# Adafruit_PCF8523_RTC.net
KiCad netlist of a schematic drawn in EAGLE
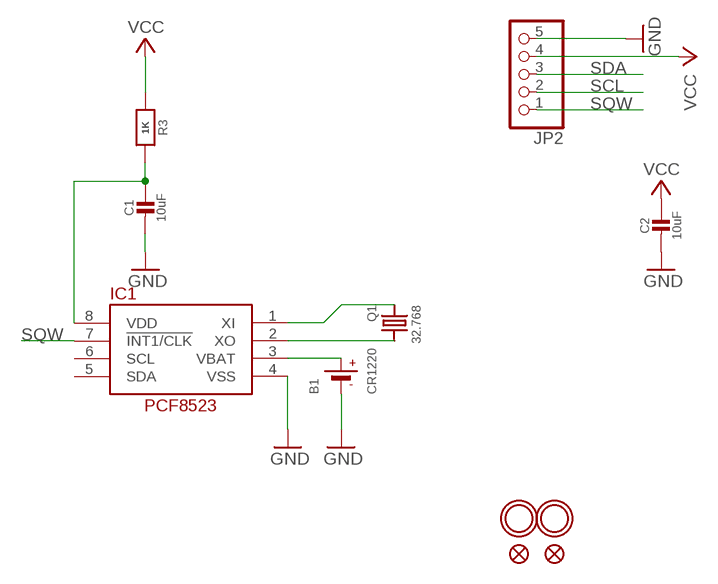
[diagram p0: schematic, sheet 1]

(export (version "E")
  (design (tool "Eeschema 10.0.6"))
  (components
    (comp (ref "B1")
      (value "CR1220")
      (footprint "eagle-import:CR1220")
      (libsource (lib "eagle-import") (part "BATTERYCR1220_SMT"))
    )
    (comp (ref "C1")
      (value "10uF")
      (footprint "eagle-import:0805-NO")
      (libsource (lib "eagle-import") (part "CAP_CERAMIC0805-NOOUTLINE"))
    )
    (comp (ref "C2")
      (value "10uF")
      (footprint "eagle-import:0805-NO")
      (libsource (lib "eagle-import") (part "CAP_CERAMIC0805-NOOUTLINE"))
    )
    (comp (ref "FID1")
      (value "FIDUCIAL\"\"")
      (footprint "eagle-import:FIDUCIAL_1MM")
      (libsource (lib "eagle-import") (part "FIDUCIAL{dblquote}{dblquote}"))
    )
    (comp (ref "FID2")
      (value "FIDUCIAL\"\"")
      (footprint "eagle-import:FIDUCIAL_1MM")
      (libsource (lib "eagle-import") (part "FIDUCIAL{dblquote}{dblquote}"))
    )
    (comp (ref "IC1")
      (value "RTC_PCF8523T")
      (footprint "eagle-import:SOIC8_150MIL")
      (libsource (lib "eagle-import") (part "RTC_PCF8523T"))
    )
    (comp (ref "JP2")
      (value "HEADER-1X576MIL")
      (footprint "eagle-import:1X05_ROUND_76")
      (libsource (lib "eagle-import") (part "HEADER-1X576MIL"))
    )
    (comp (ref "Q1")
      (value "32.768")
      (footprint "eagle-import:CRYSTAL_8X3.8")
      (libsource (lib "eagle-import") (part "CRYSTAL8.0X3.8"))
    )
    (comp (ref "R3")
      (value "1K")
      (footprint "eagle-import:0805-NO")
      (libsource (lib "eagle-import") (part "RESISTOR0805_NOOUTLINE"))
    )
    (comp (ref "U$1")
      (value "MOUNTINGHOLE2.0")
      (footprint "eagle-import:MOUNTINGHOLE_2.0_PLATED")
      (libsource (lib "eagle-import") (part "MOUNTINGHOLE2.0"))
    )
    (comp (ref "U$4")
      (value "MOUNTINGHOLE2.0")
      (footprint "eagle-import:MOUNTINGHOLE_2.0_PLATED")
      (libsource (lib "eagle-import") (part "MOUNTINGHOLE2.0"))
    )
  )
  (nets
    (net (code "1") (name "/SCL") (class "Default")
      (node (ref "JP2") (pin "2") (pinfunction "2_2") (pintype "passive"))
    )
    (net (code "2") (name "/SDA") (class "Default")
      (node (ref "JP2") (pin "3") (pinfunction "3_3") (pintype "passive"))
    )
    (net (code "3") (name "/SQW") (class "Default")
      (node (ref "IC1") (pin "7") (pinfunction "~{INT1/CLK}_7") (pintype "output"))
      (node (ref "JP2") (pin "1") (pinfunction "1_1") (pintype "passive"))
    )
    (net (code "4") (name "GND") (class "Default")
      (node (ref "B1") (pin "-") (pinfunction "-_-") (pintype "passive"))
      (node (ref "C1") (pin "2") (pinfunction "2_2") (pintype "passive"))
      (node (ref "C2") (pin "2") (pinfunction "2_2") (pintype "passive"))
      (node (ref "IC1") (pin "4") (pinfunction "VSS_4") (pintype "power_in"))
      (node (ref "JP2") (pin "5") (pinfunction "5_5") (pintype "passive"))
    )
    (net (code "5") (name "Net-(B1-+)") (class "Default")
      (node (ref "B1") (pin "+$1") (pinfunction "+_+$1") (pintype "passive"))
      (node (ref "IC1") (pin "3") (pinfunction "VBAT_3") (pintype "power_in"))
    )
    (net (code "6") (name "Net-(IC1-VDD)") (class "Default")
      (node (ref "C1") (pin "1") (pinfunction "1_1") (pintype "passive"))
      (node (ref "IC1") (pin "8") (pinfunction "VDD_8") (pintype "power_in"))
      (node (ref "R3") (pin "2") (pinfunction "2_2") (pintype "passive"))
    )
    (net (code "7") (name "Net-(IC1-XI)") (class "Default")
      (node (ref "IC1") (pin "1") (pinfunction "XI_1") (pintype "input"))
      (node (ref "Q1") (pin "P$1") (pinfunction "1_P$1") (pintype "passive"))
    )
    (net (code "8") (name "Net-(IC1-XO)") (class "Default")
      (node (ref "IC1") (pin "2") (pinfunction "XO_2") (pintype "output"))
      (node (ref "Q1") (pin "P$4") (pinfunction "2_P$4") (pintype "passive"))
    )
    (net (code "9") (name "VCC") (class "Default")
      (node (ref "C2") (pin "1") (pinfunction "1_1") (pintype "passive"))
      (node (ref "JP2") (pin "4") (pinfunction "4_4") (pintype "passive"))
      (node (ref "R3") (pin "1") (pinfunction "1_1") (pintype "passive"))
    )
    (net (code "10") (name "unconnected-(IC1-SCL-Pad6)") (class "Default")
      (node (ref "IC1") (pin "6") (pinfunction "SCL_6") (pintype "bidirectional"))
    )
    (net (code "11") (name "unconnected-(IC1-SDA-Pad5)") (class "Default")
      (node (ref "IC1") (pin "5") (pinfunction "SDA_5") (pintype "bidirectional"))
    )
  )
)
